# V3.net
KiCad netlist of a schematic drawn in EAGLE
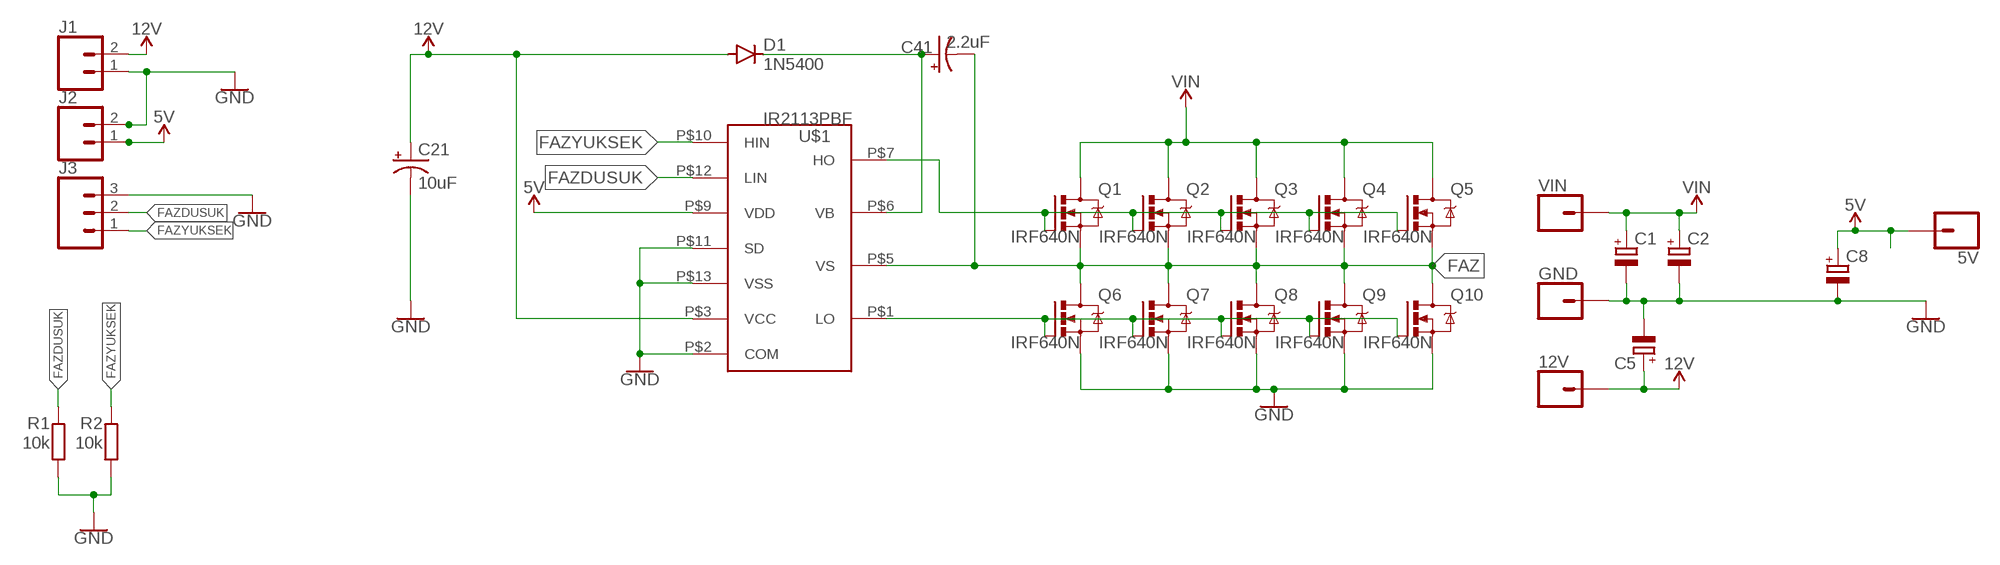
[diagram p0: schematic, sheet 1]

(export (version "E")
  (design (tool "Eeschema 10.0.6"))
  (components
    (comp (ref "5V")
      (value "CONN_01SNAP-MALE")
      (footprint "eagle-import:SNAP-MALE")
      (libsource (lib "eagle-import") (part "CONN_01SNAP-MALE"))
    )
    (comp (ref "12V")
      (value "CONN_01SNAP-MALE")
      (footprint "eagle-import:SNAP-MALE")
      (libsource (lib "eagle-import") (part "CONN_01SNAP-MALE"))
    )
    (comp (ref "C1")
      (value "16MM-DIA-CAPASITOR")
      (footprint "eagle-import:16MM-DIA-CAPASITOR")
      (libsource (lib "eagle-import") (part "16MM-DIA-CAPASITOR"))
    )
    (comp (ref "C2")
      (value "16MM-DIA-CAPASITOR")
      (footprint "eagle-import:16MM-DIA-CAPASITOR")
      (libsource (lib "eagle-import") (part "16MM-DIA-CAPASITOR"))
    )
    (comp (ref "C5")
      (value "16MM-DIA-CAPASITOR")
      (footprint "eagle-import:16MM-DIA-CAPASITOR")
      (libsource (lib "eagle-import") (part "16MM-DIA-CAPASITOR"))
    )
    (comp (ref "C8")
      (value "16MM-DIA-CAPASITOR")
      (footprint "eagle-import:16MM-DIA-CAPASITOR")
      (libsource (lib "eagle-import") (part "16MM-DIA-CAPASITOR"))
    )
    (comp (ref "C21")
      (value "10uF")
      (footprint "eagle-import:CPOL-RADIAL-2.5MM-5MM")
      (libsource (lib "eagle-import") (part "10UF-POLAR-RADIAL-2.5MM-25V-20%"))
    )
    (comp (ref "C41")
      (value "2.2uF")
      (footprint "eagle-import:CPOL-RADIAL-2.5MM-5MM")
      (libsource (lib "eagle-import") (part "10UF-POLAR-RADIAL-2.5MM-25V-20%"))
    )
    (comp (ref "D1")
      (value "1N5400")
      (footprint "eagle-import:DO201-15")
      (libsource (lib "eagle-import") (part "1N5400"))
    )
    (comp (ref "GND")
      (value "CONN_01SNAP-MALE")
      (footprint "eagle-import:SNAP-MALE")
      (libsource (lib "eagle-import") (part "CONN_01SNAP-MALE"))
    )
    (comp (ref "J1")
      (value "CONN_025MM")
      (footprint "eagle-import:SCREWTERMINAL-5MM-2")
      (libsource (lib "eagle-import") (part "CONN_025MM"))
    )
    (comp (ref "J2")
      (value "CONN_025MM")
      (footprint "eagle-import:SCREWTERMINAL-5MM-2")
      (libsource (lib "eagle-import") (part "CONN_025MM"))
    )
    (comp (ref "J3")
      (value "CONN_03-SCREW-5MM")
      (footprint "eagle-import:SCREWTERMINAL-5MM-3")
      (libsource (lib "eagle-import") (part "CONN_03-SCREW-5MM"))
    )
    (comp (ref "Q1")
      (value "IRF640N")
      (footprint "eagle-import:TO-220-PAD")
      (libsource (lib "eagle-import") (part "IRF640N"))
    )
    (comp (ref "Q2")
      (value "IRF640N")
      (footprint "eagle-import:TO-220-PAD")
      (libsource (lib "eagle-import") (part "IRF640N"))
    )
    (comp (ref "Q3")
      (value "IRF640N")
      (footprint "eagle-import:TO-220-PAD")
      (libsource (lib "eagle-import") (part "IRF640N"))
    )
    (comp (ref "Q4")
      (value "IRF640N")
      (footprint "eagle-import:TO-220-PAD")
      (libsource (lib "eagle-import") (part "IRF640N"))
    )
    (comp (ref "Q5")
      (value "IRF640N")
      (footprint "eagle-import:TO-220-PAD")
      (libsource (lib "eagle-import") (part "IRF640N"))
    )
    (comp (ref "Q6")
      (value "IRF640N")
      (footprint "eagle-import:TO-220-PAD")
      (libsource (lib "eagle-import") (part "IRF640N"))
    )
    (comp (ref "Q7")
      (value "IRF640N")
      (footprint "eagle-import:TO-220-PAD")
      (libsource (lib "eagle-import") (part "IRF640N"))
    )
    (comp (ref "Q8")
      (value "IRF640N")
      (footprint "eagle-import:TO-220-PAD")
      (libsource (lib "eagle-import") (part "IRF640N"))
    )
    (comp (ref "Q9")
      (value "IRF640N")
      (footprint "eagle-import:TO-220-PAD")
      (libsource (lib "eagle-import") (part "IRF640N"))
    )
    (comp (ref "Q10")
      (value "IRF640N")
      (footprint "eagle-import:TO-220-PAD")
      (libsource (lib "eagle-import") (part "IRF640N"))
    )
    (comp (ref "R1")
      (value "10k")
      (footprint "eagle-import:0207_10")
      (libsource (lib "eagle-import") (part "R-EU_0207/10"))
    )
    (comp (ref "R2")
      (value "10k")
      (footprint "eagle-import:0207_10")
      (libsource (lib "eagle-import") (part "R-EU_0207/10"))
    )
    (comp (ref "U$1")
      (value "IR2113PBF")
      (footprint "eagle-import:PDIP-14")
      (libsource (lib "eagle-import") (part "IR2113PBF"))
    )
    (comp (ref "VIN")
      (value "CONN_01SNAP-MALE")
      (footprint "eagle-import:SNAP-MALE")
      (libsource (lib "eagle-import") (part "CONN_01SNAP-MALE"))
    )
  )
  (nets
    (net (code "1") (name "5V") (class "Default")
      (node (ref "5V") (pin "2") (pinfunction "1_2") (pintype "passive"))
      (node (ref "C8") (pin "+") (pinfunction "+_+") (pintype "passive"))
      (node (ref "J2") (pin "1") (pinfunction "1_1") (pintype "passive"))
      (node (ref "U$1") (pin "P$9") (pinfunction "VDD_P$9") (pintype "bidirectional"))
    )
    (net (code "2") (name "12V") (class "Default")
      (node (ref "12V") (pin "2") (pinfunction "1_2") (pintype "passive"))
      (node (ref "C21") (pin "1") (pinfunction "+_1") (pintype "passive"))
      (node (ref "C5") (pin "+") (pinfunction "+_+") (pintype "passive"))
      (node (ref "D1") (pin "A") (pinfunction "A_A") (pintype "passive"))
      (node (ref "J1") (pin "2") (pinfunction "2_2") (pintype "passive"))
      (node (ref "U$1") (pin "P$3") (pinfunction "VCC_P$3") (pintype "bidirectional"))
    )
    (net (code "3") (name "FAZ") (class "Default")
      (node (ref "C41") (pin "2") (pinfunction "-_2") (pintype "passive"))
      (node (ref "Q1") (pin "3") (pinfunction "S_3") (pintype "passive"))
      (node (ref "Q10") (pin "TAB") (pinfunction "D_TAB") (pintype "passive"))
      (node (ref "Q2") (pin "3") (pinfunction "S_3") (pintype "passive"))
      (node (ref "Q3") (pin "3") (pinfunction "S_3") (pintype "passive"))
      (node (ref "Q4") (pin "3") (pinfunction "S_3") (pintype "passive"))
      (node (ref "Q5") (pin "3") (pinfunction "S_3") (pintype "passive"))
      (node (ref "Q6") (pin "TAB") (pinfunction "D_TAB") (pintype "passive"))
      (node (ref "Q7") (pin "TAB") (pinfunction "D_TAB") (pintype "passive"))
      (node (ref "Q8") (pin "TAB") (pinfunction "D_TAB") (pintype "passive"))
      (node (ref "Q9") (pin "TAB") (pinfunction "D_TAB") (pintype "passive"))
      (node (ref "U$1") (pin "P$5") (pinfunction "VS_P$5") (pintype "bidirectional"))
    )
    (net (code "4") (name "FAZDUSUK") (class "Default")
      (node (ref "J3") (pin "2") (pinfunction "2_2") (pintype "passive"))
      (node (ref "R1") (pin "2") (pinfunction "2_2") (pintype "passive"))
      (node (ref "U$1") (pin "P$12") (pinfunction "LIN_P$12") (pintype "bidirectional"))
    )
    (net (code "5") (name "FAZYUKSEK") (class "Default")
      (node (ref "J3") (pin "1") (pinfunction "1_1") (pintype "passive"))
      (node (ref "R2") (pin "2") (pinfunction "2_2") (pintype "passive"))
      (node (ref "U$1") (pin "P$10") (pinfunction "HIN_P$10") (pintype "bidirectional"))
    )
    (net (code "6") (name "GND") (class "Default")
      (node (ref "C1") (pin "-") (pinfunction "-_-") (pintype "passive"))
      (node (ref "C2") (pin "-") (pinfunction "-_-") (pintype "passive"))
      (node (ref "C21") (pin "2") (pinfunction "-_2") (pintype "passive"))
      (node (ref "C5") (pin "-") (pinfunction "-_-") (pintype "passive"))
      (node (ref "C8") (pin "-") (pinfunction "-_-") (pintype "passive"))
      (node (ref "GND") (pin "2") (pinfunction "1_2") (pintype "passive"))
      (node (ref "J1") (pin "1") (pinfunction "1_1") (pintype "passive"))
      (node (ref "J2") (pin "2") (pinfunction "2_2") (pintype "passive"))
      (node (ref "J3") (pin "3") (pinfunction "3_3") (pintype "passive"))
      (node (ref "Q10") (pin "3") (pinfunction "S_3") (pintype "passive"))
      (node (ref "Q6") (pin "3") (pinfunction "S_3") (pintype "passive"))
      (node (ref "Q7") (pin "3") (pinfunction "S_3") (pintype "passive"))
      (node (ref "Q8") (pin "3") (pinfunction "S_3") (pintype "passive"))
      (node (ref "Q9") (pin "3") (pinfunction "S_3") (pintype "passive"))
      (node (ref "R1") (pin "1") (pinfunction "1_1") (pintype "passive"))
      (node (ref "R2") (pin "1") (pinfunction "1_1") (pintype "passive"))
      (node (ref "U$1") (pin "P$11") (pinfunction "SD_P$11") (pintype "bidirectional"))
      (node (ref "U$1") (pin "P$13") (pinfunction "VSS_P$13") (pintype "bidirectional"))
      (node (ref "U$1") (pin "P$2") (pinfunction "COM_P$2") (pintype "bidirectional"))
    )
    (net (code "7") (name "Net-(C41-+)") (class "Default")
      (node (ref "C41") (pin "1") (pinfunction "+_1") (pintype "passive"))
      (node (ref "D1") (pin "C") (pinfunction "C_C") (pintype "passive"))
      (node (ref "U$1") (pin "P$6") (pinfunction "VB_P$6") (pintype "bidirectional"))
    )
    (net (code "8") (name "Net-(Q1-G)") (class "Default")
      (node (ref "Q1") (pin "1") (pinfunction "G_1") (pintype "passive"))
      (node (ref "Q2") (pin "1") (pinfunction "G_1") (pintype "passive"))
      (node (ref "Q3") (pin "1") (pinfunction "G_1") (pintype "passive"))
      (node (ref "Q4") (pin "1") (pinfunction "G_1") (pintype "passive"))
      (node (ref "Q5") (pin "1") (pinfunction "G_1") (pintype "passive"))
      (node (ref "U$1") (pin "P$7") (pinfunction "HO_P$7") (pintype "bidirectional"))
    )
    (net (code "9") (name "Net-(Q10-G)") (class "Default")
      (node (ref "Q10") (pin "1") (pinfunction "G_1") (pintype "passive"))
      (node (ref "Q6") (pin "1") (pinfunction "G_1") (pintype "passive"))
      (node (ref "Q7") (pin "1") (pinfunction "G_1") (pintype "passive"))
      (node (ref "Q8") (pin "1") (pinfunction "G_1") (pintype "passive"))
      (node (ref "Q9") (pin "1") (pinfunction "G_1") (pintype "passive"))
      (node (ref "U$1") (pin "P$1") (pinfunction "LO_P$1") (pintype "bidirectional"))
    )
    (net (code "10") (name "VIN") (class "Default")
      (node (ref "C1") (pin "+") (pinfunction "+_+") (pintype "passive"))
      (node (ref "C2") (pin "+") (pinfunction "+_+") (pintype "passive"))
      (node (ref "Q1") (pin "TAB") (pinfunction "D_TAB") (pintype "passive"))
      (node (ref "Q2") (pin "TAB") (pinfunction "D_TAB") (pintype "passive"))
      (node (ref "Q3") (pin "TAB") (pinfunction "D_TAB") (pintype "passive"))
      (node (ref "Q4") (pin "TAB") (pinfunction "D_TAB") (pintype "passive"))
      (node (ref "Q5") (pin "TAB") (pinfunction "D_TAB") (pintype "passive"))
      (node (ref "VIN") (pin "2") (pinfunction "1_2") (pintype "passive"))
    )
  )
)
